# NBT_RS_232.net
KiCad netlist of a schematic drawn in Altium Designer
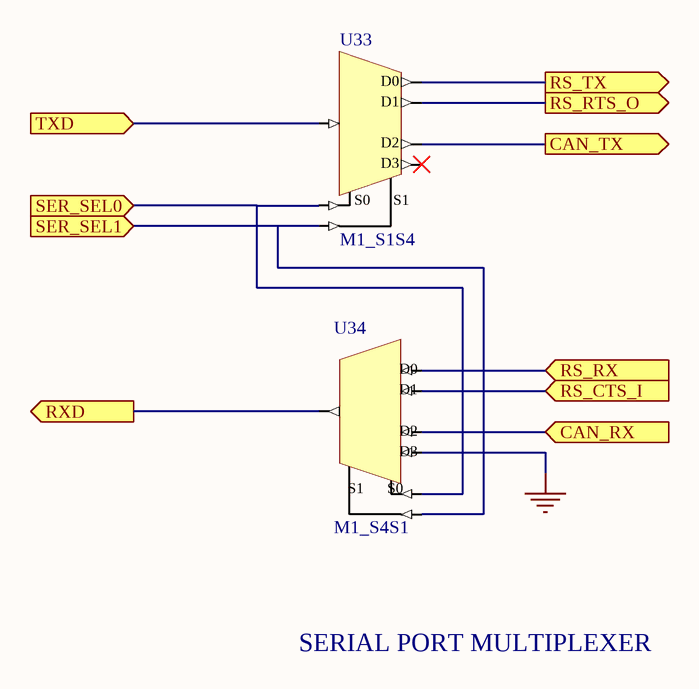
[diagram p0: NBT_RS_232.SCHDOC]

(export (version "E")
  (design (tool "Eeschema 10.0.6"))
  (components
    (comp (ref "U33")
      (value "M1_S1S4")
      (description "1x1-Single Wire to 4x1-Single Wire Multiplexer (Demultiplex)")
      (fields (field (name "PUBLISHER") "Altium Limited"))
      (libsource (lib "FPGA Generic") (part "M1_S1S4"))
    )
    (comp (ref "U34")
      (value "M1_S4S1")
      (description "4x1-Single Wire to 1x1-Single Wire Multiplexer")
      (fields (field (name "PUBLISHER") "Altium Limited"))
      (libsource (lib "FPGA Generic") (part "M1_S4S1"))
    )
  )
  (nets
    (net (code "1") (name "/CAN_RX") (class "Default")
      (node (ref "U34") (pin "D2") (pinfunction "D2_D2") (pintype "input"))
    )
    (net (code "2") (name "/CAN_TX") (class "Default")
      (node (ref "U33") (pin "D2") (pinfunction "D2_D2") (pintype "output"))
    )
    (net (code "3") (name "/RS_CTS_I") (class "Default")
      (node (ref "U34") (pin "D1") (pinfunction "D1_D1") (pintype "input"))
    )
    (net (code "4") (name "/RS_RTS_O") (class "Default")
      (node (ref "U33") (pin "D1") (pinfunction "D1_D1") (pintype "output"))
    )
    (net (code "5") (name "/RS_RX") (class "Default")
      (node (ref "U34") (pin "D0") (pinfunction "D0_D0") (pintype "input"))
    )
    (net (code "6") (name "/RS_TX") (class "Default")
      (node (ref "U33") (pin "D0") (pinfunction "D0_D0") (pintype "output"))
    )
    (net (code "7") (name "/RXD") (class "Default")
      (node (ref "U34") (pin "O") (pinfunction "O_O") (pintype "output"))
    )
    (net (code "8") (name "/SER_SEL0") (class "Default")
      (node (ref "U33") (pin "S0") (pinfunction "S0_S0") (pintype "input"))
      (node (ref "U34") (pin "S0") (pinfunction "S0_S0") (pintype "input"))
    )
    (net (code "9") (name "/SER_SEL1") (class "Default")
      (node (ref "U33") (pin "S1") (pinfunction "S1_S1") (pintype "input"))
      (node (ref "U34") (pin "S1") (pinfunction "S1_S1") (pintype "input"))
    )
    (net (code "10") (name "/TXD") (class "Default")
      (node (ref "U33") (pin "O") (pinfunction "O_O") (pintype "input"))
    )
    (net (code "11") (name "GND") (class "Default")
      (node (ref "U34") (pin "D3") (pinfunction "D3_D3") (pintype "input"))
    )
    (net (code "12") (name "unconnected-(U33-PadD3)") (class "Default")
      (node (ref "U33") (pin "D3") (pinfunction "D3_D3") (pintype "output+no_connect"))
    )
  )
)
